# USB_UART_Convertors.net
KiCad netlist of a schematic drawn in Altium Designer
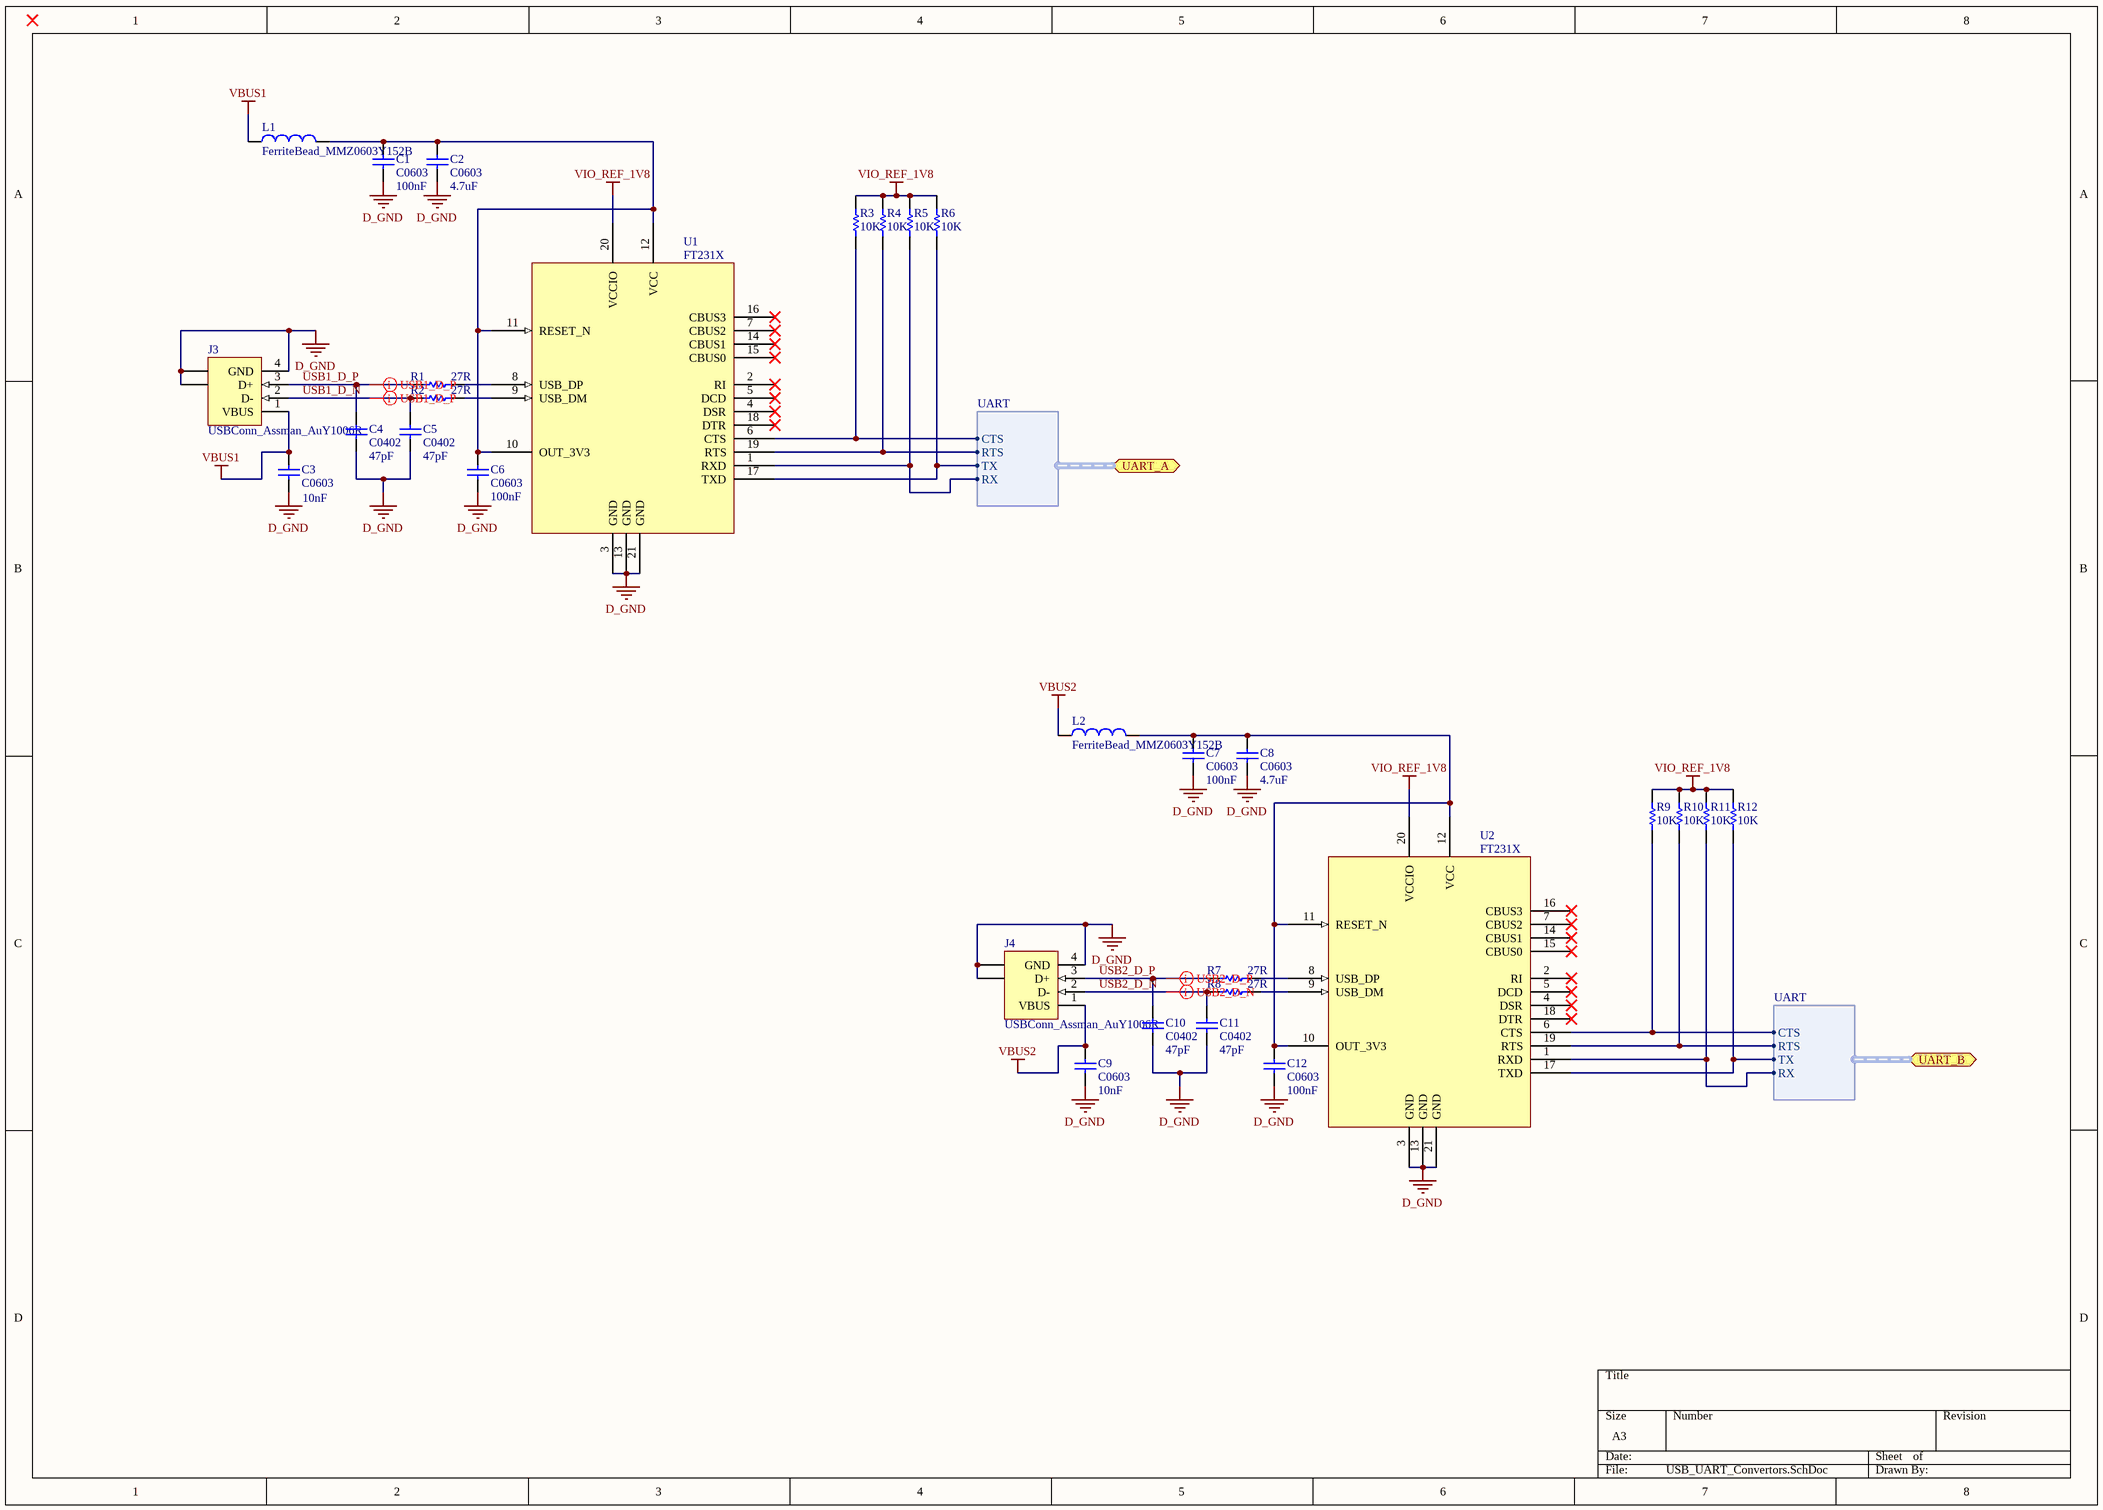
[diagram p0: USB_UART_Convertors.SchDoc]

(export (version "E")
  (design (tool "Eeschema 10.0.6"))
  (components
    (comp (ref "C1")
      (value "C0603")
      (footprint "CAP_CER_0603_KEMET:CAP_CER_0603_KEMET")
      (description "Ceramic Chip Capacitor - Standard")
      (fields (field (name "ALTIUM_VALUE") "100nF") (field (name "PUBLISHER") "Altium Limited"))
      (libsource (lib "KEMET Chip Capacitor") (part "C0603"))
    )
    (comp (ref "C2")
      (value "C0603")
      (footprint "CAP_CER_0603_KEMET:CAP_CER_0603_KEMET")
      (description "Ceramic Chip Capacitor - Standard")
      (fields (field (name "ALTIUM_VALUE") "4.7uF") (field (name "PUBLISHER") "Altium Limited"))
      (libsource (lib "KEMET Chip Capacitor") (part "C0603"))
    )
    (comp (ref "C3")
      (value "C0603")
      (footprint "CAP_CER_0603_KEMET:CAP_CER_0603_KEMET")
      (description "Ceramic Chip Capacitor - Standard")
      (fields (field (name "ALTIUM_VALUE") "10nF") (field (name "PUBLISHER") "Altium Limited"))
      (libsource (lib "KEMET Chip Capacitor") (part "C0603"))
    )
    (comp (ref "C4")
      (value "C0402")
      (footprint "CAP_CER_0402_KEMET:CAP_CER_0402_KEMET")
      (description "Ceramic Chip Capacitor - Standard")
      (fields (field (name "ALTIUM_VALUE") "47pF") (field (name "PUBLISHER") "Altium Limited"))
      (libsource (lib "KEMET Chip Capacitor") (part "C0402"))
    )
    (comp (ref "C5")
      (value "C0402")
      (footprint "CAP_CER_0402_KEMET:CAP_CER_0402_KEMET")
      (description "Ceramic Chip Capacitor - Standard")
      (fields (field (name "ALTIUM_VALUE") "47pF") (field (name "PUBLISHER") "Altium Limited"))
      (libsource (lib "KEMET Chip Capacitor") (part "C0402"))
    )
    (comp (ref "C6")
      (value "C0603")
      (footprint "CAP_CER_0603_KEMET:CAP_CER_0603_KEMET")
      (description "Ceramic Chip Capacitor - Standard")
      (fields (field (name "ALTIUM_VALUE") "100nF") (field (name "PUBLISHER") "Altium Limited"))
      (libsource (lib "KEMET Chip Capacitor") (part "C0603"))
    )
    (comp (ref "C7")
      (value "C0603")
      (footprint "CAP_CER_0603_KEMET:CAP_CER_0603_KEMET")
      (description "Ceramic Chip Capacitor - Standard")
      (fields (field (name "ALTIUM_VALUE") "100nF") (field (name "PUBLISHER") "Altium Limited"))
      (libsource (lib "KEMET Chip Capacitor") (part "C0603"))
    )
    (comp (ref "C8")
      (value "C0603")
      (footprint "CAP_CER_0603_KEMET:CAP_CER_0603_KEMET")
      (description "Ceramic Chip Capacitor - Standard")
      (fields (field (name "ALTIUM_VALUE") "4.7uF") (field (name "PUBLISHER") "Altium Limited"))
      (libsource (lib "KEMET Chip Capacitor") (part "C0603"))
    )
    (comp (ref "C9")
      (value "C0603")
      (footprint "CAP_CER_0603_KEMET:CAP_CER_0603_KEMET")
      (description "Ceramic Chip Capacitor - Standard")
      (fields (field (name "ALTIUM_VALUE") "10nF") (field (name "PUBLISHER") "Altium Limited"))
      (libsource (lib "KEMET Chip Capacitor") (part "C0603"))
    )
    (comp (ref "C10")
      (value "C0402")
      (footprint "CAP_CER_0402_KEMET:CAP_CER_0402_KEMET")
      (description "Ceramic Chip Capacitor - Standard")
      (fields (field (name "ALTIUM_VALUE") "47pF") (field (name "PUBLISHER") "Altium Limited"))
      (libsource (lib "KEMET Chip Capacitor") (part "C0402"))
    )
    (comp (ref "C11")
      (value "C0402")
      (footprint "CAP_CER_0402_KEMET:CAP_CER_0402_KEMET")
      (description "Ceramic Chip Capacitor - Standard")
      (fields (field (name "ALTIUM_VALUE") "47pF") (field (name "PUBLISHER") "Altium Limited"))
      (libsource (lib "KEMET Chip Capacitor") (part "C0402"))
    )
    (comp (ref "C12")
      (value "C0603")
      (footprint "CAP_CER_0603_KEMET:CAP_CER_0603_KEMET")
      (description "Ceramic Chip Capacitor - Standard")
      (fields (field (name "ALTIUM_VALUE") "100nF") (field (name "PUBLISHER") "Altium Limited"))
      (libsource (lib "KEMET Chip Capacitor") (part "C0603"))
    )
    (comp (ref "J3")
      (value "USBConn_Assman_AuY1006R")
      (footprint "USBConn_Assman_AuY1006R:USBConn_Assman_AuY1006R")
      (description "USB 1.1, Right Angle, SMT, A Type, Receptacle, 4 Position, White")
      (fields (field (name "PUBLISHER") "Altium Limited"))
      (libsource (lib "AMP Serial Bus USB") (part "1-353576-1"))
    )
    (comp (ref "J4")
      (value "USBConn_Assman_AuY1006R")
      (footprint "USBConn_Assman_AuY1006R:USBConn_Assman_AuY1006R")
      (description "USB 1.1, Right Angle, SMT, A Type, Receptacle, 4 Position, White")
      (fields (field (name "PUBLISHER") "Altium Limited"))
      (libsource (lib "AMP Serial Bus USB") (part "1-353576-1"))
    )
    (comp (ref "L1")
      (value "FerriteBead_MMZ0603Y152B")
      (footprint "Chip2PinSM127P600-8N_FerriteBead_TDK:Chip2PinSM127P600-8N_FerriteBead_TDK")
      (description "Inductor")
      (fields (field (name "PUBLISHER") "Altium Limited"))
      (libsource (lib "Miscellaneous Devices") (part "Inductor"))
    )
    (comp (ref "L2")
      (value "FerriteBead_MMZ0603Y152B")
      (footprint "Chip2PinSM127P600-8N_FerriteBead_TDK:Chip2PinSM127P600-8N_FerriteBead_TDK")
      (description "Inductor")
      (fields (field (name "PUBLISHER") "Altium Limited"))
      (libsource (lib "Miscellaneous Devices") (part "Inductor"))
    )
    (comp (ref "R1")
      (value "27R")
      (footprint "RES_CHIP_0402:RES_CHIP_0402")
      (description "Thick Film Chip Resistor, 1 Ohm to 2.2M Ohm Range, 5% Tolerance, 0402 Size, 0.063 W")
      (fields (field (name "PUBLISHER") "Altium Limited"))
      (libsource (lib "Panasonic Resistor") (part "ERJ2GE"))
    )
    (comp (ref "R2")
      (value "27R")
      (footprint "RES_CHIP_0402:RES_CHIP_0402")
      (description "Thick Film Chip Resistor, 1 Ohm to 2.2M Ohm Range, 5% Tolerance, 0402 Size, 0.063 W")
      (fields (field (name "PUBLISHER") "Altium Limited"))
      (libsource (lib "Panasonic Resistor") (part "ERJ2GE"))
    )
    (comp (ref "R3")
      (value "10K")
      (footprint "RES_CHIP_0402:RES_CHIP_0402")
      (description "Thick Film Chip Resistor, 1 Ohm to 2.2M Ohm Range, 5% Tolerance, 0402 Size, 0.063 W")
      (fields (field (name "PUBLISHER") "Altium Limited"))
      (libsource (lib "Panasonic Resistor") (part "ERJ2GE"))
    )
    (comp (ref "R4")
      (value "10K")
      (footprint "RES_CHIP_0402:RES_CHIP_0402")
      (description "Thick Film Chip Resistor, 1 Ohm to 2.2M Ohm Range, 5% Tolerance, 0402 Size, 0.063 W")
      (fields (field (name "PUBLISHER") "Altium Limited"))
      (libsource (lib "Panasonic Resistor") (part "ERJ2GE"))
    )
    (comp (ref "R5")
      (value "10K")
      (footprint "RES_CHIP_0402:RES_CHIP_0402")
      (description "Thick Film Chip Resistor, 1 Ohm to 2.2M Ohm Range, 5% Tolerance, 0402 Size, 0.063 W")
      (fields (field (name "PUBLISHER") "Altium Limited"))
      (libsource (lib "Panasonic Resistor") (part "ERJ2GE"))
    )
    (comp (ref "R6")
      (value "10K")
      (footprint "RES_CHIP_0402:RES_CHIP_0402")
      (description "Thick Film Chip Resistor, 1 Ohm to 2.2M Ohm Range, 5% Tolerance, 0402 Size, 0.063 W")
      (fields (field (name "PUBLISHER") "Altium Limited"))
      (libsource (lib "Panasonic Resistor") (part "ERJ2GE"))
    )
    (comp (ref "R7")
      (value "27R")
      (footprint "RES_CHIP_0402:RES_CHIP_0402")
      (description "Thick Film Chip Resistor, 1 Ohm to 2.2M Ohm Range, 5% Tolerance, 0402 Size, 0.063 W")
      (fields (field (name "PUBLISHER") "Altium Limited"))
      (libsource (lib "Panasonic Resistor") (part "ERJ2GE"))
    )
    (comp (ref "R8")
      (value "27R")
      (footprint "RES_CHIP_0402:RES_CHIP_0402")
      (description "Thick Film Chip Resistor, 1 Ohm to 2.2M Ohm Range, 5% Tolerance, 0402 Size, 0.063 W")
      (fields (field (name "PUBLISHER") "Altium Limited"))
      (libsource (lib "Panasonic Resistor") (part "ERJ2GE"))
    )
    (comp (ref "R9")
      (value "10K")
      (footprint "RES_CHIP_0402:RES_CHIP_0402")
      (description "Thick Film Chip Resistor, 1 Ohm to 2.2M Ohm Range, 5% Tolerance, 0402 Size, 0.063 W")
      (fields (field (name "PUBLISHER") "Altium Limited"))
      (libsource (lib "Panasonic Resistor") (part "ERJ2GE"))
    )
    (comp (ref "R10")
      (value "10K")
      (footprint "RES_CHIP_0402:RES_CHIP_0402")
      (description "Thick Film Chip Resistor, 1 Ohm to 2.2M Ohm Range, 5% Tolerance, 0402 Size, 0.063 W")
      (fields (field (name "PUBLISHER") "Altium Limited"))
      (libsource (lib "Panasonic Resistor") (part "ERJ2GE"))
    )
    (comp (ref "R11")
      (value "10K")
      (footprint "RES_CHIP_0402:RES_CHIP_0402")
      (description "Thick Film Chip Resistor, 1 Ohm to 2.2M Ohm Range, 5% Tolerance, 0402 Size, 0.063 W")
      (fields (field (name "PUBLISHER") "Altium Limited"))
      (libsource (lib "Panasonic Resistor") (part "ERJ2GE"))
    )
    (comp (ref "R12")
      (value "10K")
      (footprint "RES_CHIP_0402:RES_CHIP_0402")
      (description "Thick Film Chip Resistor, 1 Ohm to 2.2M Ohm Range, 5% Tolerance, 0402 Size, 0.063 W")
      (fields (field (name "PUBLISHER") "Altium Limited"))
      (libsource (lib "Panasonic Resistor") (part "ERJ2GE"))
    )
    (comp (ref "U1")
      (value "FT231X")
      (footprint "QFN127P600-8N_FTDI_20PIN")
      (libsource (lib "SchlibOjonav") (part "FT231X"))
    )
    (comp (ref "U2")
      (value "FT231X")
      (footprint "QFN127P600-8N_FTDI_20PIN")
      (libsource (lib "SchlibOjonav") (part "FT231X"))
    )
  )
  (nets
    (net (code "2") (name "/USB1_D_N") (class "Default")
      (node (ref "C5") (pin "2") (pinfunction "2_2") (pintype "passive"))
      (node (ref "J3") (pin "2") (pinfunction "D-_2") (pintype "input"))
      (node (ref "R2") (pin "2") (pinfunction "2_2") (pintype "passive"))
    )
    (net (code "3") (name "/USB1_D_P") (class "Default")
      (node (ref "C4") (pin "2") (pinfunction "2_2") (pintype "passive"))
      (node (ref "J3") (pin "3") (pinfunction "D+_3") (pintype "input"))
      (node (ref "R1") (pin "2") (pinfunction "2_2") (pintype "passive"))
    )
    (net (code "4") (name "/USB2_D_N") (class "Default")
      (node (ref "C11") (pin "2") (pinfunction "2_2") (pintype "passive"))
      (node (ref "J4") (pin "2") (pinfunction "D-_2") (pintype "input"))
      (node (ref "R8") (pin "2") (pinfunction "2_2") (pintype "passive"))
    )
    (net (code "5") (name "/USB2_D_P") (class "Default")
      (node (ref "C10") (pin "2") (pinfunction "2_2") (pintype "passive"))
      (node (ref "J4") (pin "3") (pinfunction "D+_3") (pintype "input"))
      (node (ref "R7") (pin "2") (pinfunction "2_2") (pintype "passive"))
    )
    (net (code "7") (name "D_GND") (class "Default")
      (node (ref "C1") (pin "1") (pinfunction "1_1") (pintype "passive"))
      (node (ref "C10") (pin "1") (pinfunction "1_1") (pintype "passive"))
      (node (ref "C11") (pin "1") (pinfunction "1_1") (pintype "passive"))
      (node (ref "C12") (pin "1") (pinfunction "1_1") (pintype "passive"))
      (node (ref "C2") (pin "1") (pinfunction "1_1") (pintype "passive"))
      (node (ref "C3") (pin "1") (pinfunction "1_1") (pintype "passive"))
      (node (ref "C4") (pin "1") (pinfunction "1_1") (pintype "passive"))
      (node (ref "C5") (pin "1") (pinfunction "1_1") (pintype "passive"))
      (node (ref "C6") (pin "1") (pinfunction "1_1") (pintype "passive"))
      (node (ref "C7") (pin "1") (pinfunction "1_1") (pintype "passive"))
      (node (ref "C8") (pin "1") (pinfunction "1_1") (pintype "passive"))
      (node (ref "C9") (pin "1") (pinfunction "1_1") (pintype "passive"))
      (node (ref "J3") (pin "4") (pinfunction "GND_4") (pintype "power_in"))
      (node (ref "J3") (pin "5") (pinfunction "SHLD_5") (pintype "passive"))
      (node (ref "J3") (pin "6") (pinfunction "SHLD_6") (pintype "passive"))
      (node (ref "J4") (pin "4") (pinfunction "GND_4") (pintype "power_in"))
      (node (ref "J4") (pin "5") (pinfunction "SHLD_5") (pintype "passive"))
      (node (ref "J4") (pin "6") (pinfunction "SHLD_6") (pintype "passive"))
      (node (ref "U1") (pin "13") (pinfunction "GND_13") (pintype "power_in"))
      (node (ref "U1") (pin "21") (pinfunction "GND_21") (pintype "power_in"))
      (node (ref "U1") (pin "3") (pinfunction "GND_3") (pintype "power_in"))
      (node (ref "U2") (pin "13") (pinfunction "GND_13") (pintype "power_in"))
      (node (ref "U2") (pin "21") (pinfunction "GND_21") (pintype "power_in"))
      (node (ref "U2") (pin "3") (pinfunction "GND_3") (pintype "power_in"))
    )
    (net (code "8") (name "Net-(U1-CTS)") (class "Default")
      (node (ref "R3") (pin "1") (pinfunction "1_1") (pintype "passive"))
      (node (ref "U1") (pin "6") (pinfunction "CTS_6") (pintype "passive"))
    )
    (net (code "9") (name "Net-(U1-OUT_3V3)") (class "Default")
      (node (ref "C1") (pin "2") (pinfunction "2_2") (pintype "passive"))
      (node (ref "C2") (pin "2") (pinfunction "2_2") (pintype "passive"))
      (node (ref "C6") (pin "2") (pinfunction "2_2") (pintype "passive"))
      (node (ref "L1") (pin "2") (pinfunction "2_2") (pintype "passive"))
      (node (ref "U1") (pin "10") (pinfunction "OUT_3V3_10") (pintype "power_in"))
      (node (ref "U1") (pin "11") (pinfunction "RESET_N_11") (pintype "input"))
      (node (ref "U1") (pin "12") (pinfunction "VCC_12") (pintype "passive"))
    )
    (net (code "10") (name "Net-(U1-RTS)") (class "Default")
      (node (ref "R4") (pin "1") (pinfunction "1_1") (pintype "passive"))
      (node (ref "U1") (pin "19") (pinfunction "RTS_19") (pintype "passive"))
    )
    (net (code "11") (name "Net-(U1-RXD)") (class "Default")
      (node (ref "R5") (pin "1") (pinfunction "1_1") (pintype "passive"))
      (node (ref "U1") (pin "1") (pinfunction "RXD_1") (pintype "passive"))
    )
    (net (code "12") (name "Net-(U1-TXD)") (class "Default")
      (node (ref "R6") (pin "1") (pinfunction "1_1") (pintype "passive"))
      (node (ref "U1") (pin "17") (pinfunction "TXD_17") (pintype "passive"))
    )
    (net (code "13") (name "Net-(U1-USB_DM)") (class "Default")
      (node (ref "R2") (pin "1") (pinfunction "1_1") (pintype "passive"))
      (node (ref "U1") (pin "9") (pinfunction "USB_DM_9") (pintype "input"))
    )
    (net (code "14") (name "Net-(U1-USB_DP)") (class "Default")
      (node (ref "R1") (pin "1") (pinfunction "1_1") (pintype "passive"))
      (node (ref "U1") (pin "8") (pinfunction "USB_DP_8") (pintype "input"))
    )
    (net (code "15") (name "Net-(U2-CTS)") (class "Default")
      (node (ref "R9") (pin "1") (pinfunction "1_1") (pintype "passive"))
      (node (ref "U2") (pin "6") (pinfunction "CTS_6") (pintype "passive"))
    )
    (net (code "16") (name "Net-(U2-OUT_3V3)") (class "Default")
      (node (ref "C12") (pin "2") (pinfunction "2_2") (pintype "passive"))
      (node (ref "C7") (pin "2") (pinfunction "2_2") (pintype "passive"))
      (node (ref "C8") (pin "2") (pinfunction "2_2") (pintype "passive"))
      (node (ref "L2") (pin "2") (pinfunction "2_2") (pintype "passive"))
      (node (ref "U2") (pin "10") (pinfunction "OUT_3V3_10") (pintype "power_in"))
      (node (ref "U2") (pin "11") (pinfunction "RESET_N_11") (pintype "input"))
      (node (ref "U2") (pin "12") (pinfunction "VCC_12") (pintype "passive"))
    )
    (net (code "17") (name "Net-(U2-RTS)") (class "Default")
      (node (ref "R10") (pin "1") (pinfunction "1_1") (pintype "passive"))
      (node (ref "U2") (pin "19") (pinfunction "RTS_19") (pintype "passive"))
    )
    (net (code "18") (name "Net-(U2-RXD)") (class "Default")
      (node (ref "R11") (pin "1") (pinfunction "1_1") (pintype "passive"))
      (node (ref "U2") (pin "1") (pinfunction "RXD_1") (pintype "passive"))
    )
    (net (code "19") (name "Net-(U2-TXD)") (class "Default")
      (node (ref "R12") (pin "1") (pinfunction "1_1") (pintype "passive"))
      (node (ref "U2") (pin "17") (pinfunction "TXD_17") (pintype "passive"))
    )
    (net (code "20") (name "Net-(U2-USB_DM)") (class "Default")
      (node (ref "R8") (pin "1") (pinfunction "1_1") (pintype "passive"))
      (node (ref "U2") (pin "9") (pinfunction "USB_DM_9") (pintype "input"))
    )
    (net (code "21") (name "Net-(U2-USB_DP)") (class "Default")
      (node (ref "R7") (pin "1") (pinfunction "1_1") (pintype "passive"))
      (node (ref "U2") (pin "8") (pinfunction "USB_DP_8") (pintype "input"))
    )
    (net (code "22") (name "VBUS1") (class "Default")
      (node (ref "C3") (pin "2") (pinfunction "2_2") (pintype "passive"))
      (node (ref "J3") (pin "1") (pinfunction "VBUS_1") (pintype "power_in"))
      (node (ref "L1") (pin "1") (pinfunction "1_1") (pintype "passive"))
    )
    (net (code "23") (name "VBUS2") (class "Default")
      (node (ref "C9") (pin "2") (pinfunction "2_2") (pintype "passive"))
      (node (ref "J4") (pin "1") (pinfunction "VBUS_1") (pintype "power_in"))
      (node (ref "L2") (pin "1") (pinfunction "1_1") (pintype "passive"))
    )
    (net (code "24") (name "VIO_REF_1V8") (class "Default")
      (node (ref "R10") (pin "2") (pinfunction "2_2") (pintype "passive"))
      (node (ref "R11") (pin "2") (pinfunction "2_2") (pintype "passive"))
      (node (ref "R12") (pin "2") (pinfunction "2_2") (pintype "passive"))
      (node (ref "R3") (pin "2") (pinfunction "2_2") (pintype "passive"))
      (node (ref "R4") (pin "2") (pinfunction "2_2") (pintype "passive"))
      (node (ref "R5") (pin "2") (pinfunction "2_2") (pintype "passive"))
      (node (ref "R6") (pin "2") (pinfunction "2_2") (pintype "passive"))
      (node (ref "R9") (pin "2") (pinfunction "2_2") (pintype "passive"))
      (node (ref "U1") (pin "20") (pinfunction "VCCIO_20") (pintype "power_in"))
      (node (ref "U2") (pin "20") (pinfunction "VCCIO_20") (pintype "power_in"))
    )
    (net (code "25") (name "unconnected-(U1-CBUS0-Pad15)") (class "Default")
      (node (ref "U1") (pin "15") (pinfunction "CBUS0_15") (pintype "passive+no_connect"))
    )
    (net (code "26") (name "unconnected-(U1-CBUS1-Pad14)") (class "Default")
      (node (ref "U1") (pin "14") (pinfunction "CBUS1_14") (pintype "passive+no_connect"))
    )
    (net (code "27") (name "unconnected-(U1-CBUS2-Pad7)") (class "Default")
      (node (ref "U1") (pin "7") (pinfunction "CBUS2_7") (pintype "passive+no_connect"))
    )
    (net (code "28") (name "unconnected-(U1-CBUS3-Pad16)") (class "Default")
      (node (ref "U1") (pin "16") (pinfunction "CBUS3_16") (pintype "passive+no_connect"))
    )
    (net (code "29") (name "unconnected-(U1-DCD-Pad5)") (class "Default")
      (node (ref "U1") (pin "5") (pinfunction "DCD_5") (pintype "passive+no_connect"))
    )
    (net (code "30") (name "unconnected-(U1-DSR-Pad4)") (class "Default")
      (node (ref "U1") (pin "4") (pinfunction "DSR_4") (pintype "passive+no_connect"))
    )
    (net (code "31") (name "unconnected-(U1-DTR-Pad18)") (class "Default")
      (node (ref "U1") (pin "18") (pinfunction "DTR_18") (pintype "passive+no_connect"))
    )
    (net (code "32") (name "unconnected-(U1-RI-Pad2)") (class "Default")
      (node (ref "U1") (pin "2") (pinfunction "RI_2") (pintype "passive+no_connect"))
    )
    (net (code "33") (name "unconnected-(U2-CBUS0-Pad15)") (class "Default")
      (node (ref "U2") (pin "15") (pinfunction "CBUS0_15") (pintype "passive+no_connect"))
    )
    (net (code "34") (name "unconnected-(U2-CBUS1-Pad14)") (class "Default")
      (node (ref "U2") (pin "14") (pinfunction "CBUS1_14") (pintype "passive+no_connect"))
    )
    (net (code "35") (name "unconnected-(U2-CBUS2-Pad7)") (class "Default")
      (node (ref "U2") (pin "7") (pinfunction "CBUS2_7") (pintype "passive+no_connect"))
    )
    (net (code "36") (name "unconnected-(U2-CBUS3-Pad16)") (class "Default")
      (node (ref "U2") (pin "16") (pinfunction "CBUS3_16") (pintype "passive+no_connect"))
    )
    (net (code "37") (name "unconnected-(U2-DCD-Pad5)") (class "Default")
      (node (ref "U2") (pin "5") (pinfunction "DCD_5") (pintype "passive+no_connect"))
    )
    (net (code "38") (name "unconnected-(U2-DSR-Pad4)") (class "Default")
      (node (ref "U2") (pin "4") (pinfunction "DSR_4") (pintype "passive+no_connect"))
    )
    (net (code "39") (name "unconnected-(U2-DTR-Pad18)") (class "Default")
      (node (ref "U2") (pin "18") (pinfunction "DTR_18") (pintype "passive+no_connect"))
    )
    (net (code "40") (name "unconnected-(U2-RI-Pad2)") (class "Default")
      (node (ref "U2") (pin "2") (pinfunction "RI_2") (pintype "passive+no_connect"))
    )
  )
)
